# VEHICLE_RAW_SCH.net
KiCad netlist of a schematic drawn in Altium Designer
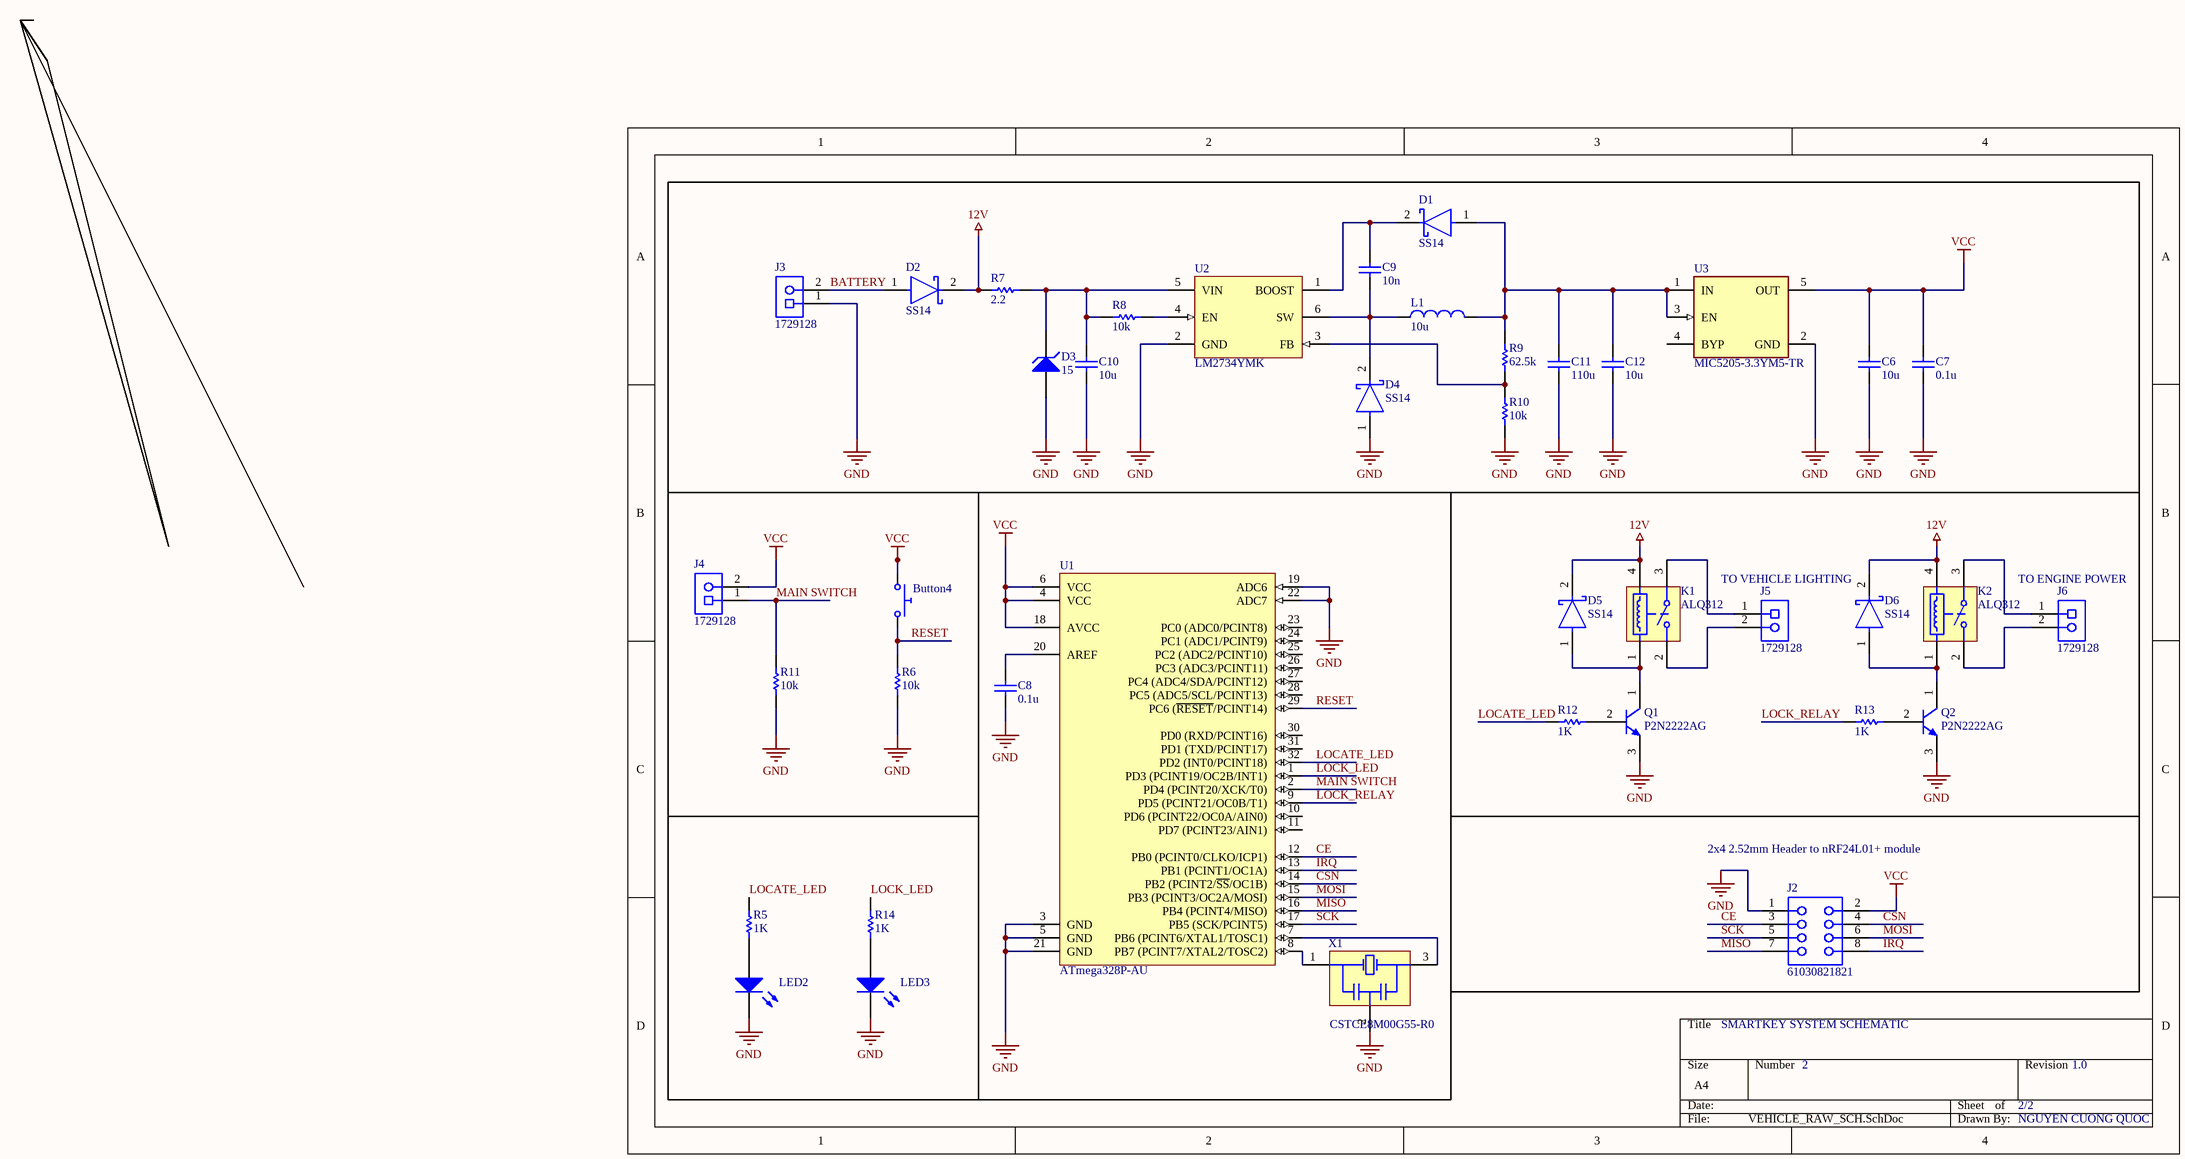
[diagram p0: VEHICLE_RAW_SCH.SchDoc]

(export (version "E")
  (design (tool "Eeschema 10.0.6"))
  (components
    (comp (ref "Button4")
      (value "Push Button Normally Opened")
      (libsource (lib "Simulation Generic Components") (part "Push Button NO"))
    )
    (comp (ref "C6")
      (value "10u")
      (description "Capacitor")
      (libsource (lib "Simulation Generic Components") (part "Capacitor"))
    )
    (comp (ref "C7")
      (value "0.1u")
      (description "Capacitor")
      (libsource (lib "Simulation Generic Components") (part "Capacitor"))
    )
    (comp (ref "C8")
      (value "0.1u")
      (description "Capacitor")
      (libsource (lib "Simulation Generic Components") (part "Capacitor"))
    )
    (comp (ref "C9")
      (value "10n")
      (description "Capacitor")
      (libsource (lib "Simulation Generic Components") (part "Capacitor"))
    )
    (comp (ref "C10")
      (value "10u")
      (description "Capacitor")
      (libsource (lib "Simulation Generic Components") (part "Capacitor"))
    )
    (comp (ref "C11")
      (value "110u")
      (description "Capacitor")
      (libsource (lib "Simulation Generic Components") (part "Capacitor"))
    )
    (comp (ref "C12")
      (value "10u")
      (description "Capacitor")
      (libsource (lib "Simulation Generic Components") (part "Capacitor"))
    )
    (comp (ref "D1")
      (value "SS14")
      (footprint "FP-403AE-MFG")
      (description "DIODE SCHOTTKY 40V 1A SMA")
      (fields
        (field (name "MANUFACTURER") "ON Semiconductor")
        (field (name "OCTOPART") "https://octopart.com/ss14-on+semiconductor-29205033")
      )
      (libsource (lib "Altium Content Vault") (part "360ad2f4ac25a952324d13796385471"))
    )
    (comp (ref "D2")
      (value "SS14")
      (footprint "FP-403AE-MFG")
      (description "DIODE SCHOTTKY 40V 1A SMA")
      (fields
        (field (name "MANUFACTURER") "ON Semiconductor")
        (field (name "OCTOPART") "https://octopart.com/ss14-on+semiconductor-29205033")
      )
      (libsource (lib "Altium Content Vault") (part "360ad2f4ac25a952324d13796385471"))
    )
    (comp (ref "D3")
      (value "Zener Diode")
      (fields (field (name "BV") "15"))
      (libsource (lib "Simulation Generic Components") (part "Zener Diode"))
    )
    (comp (ref "D4")
      (value "SS14")
      (footprint "FP-403AE-MFG")
      (description "DIODE SCHOTTKY 40V 1A SMA")
      (fields
        (field (name "MANUFACTURER") "ON Semiconductor")
        (field (name "OCTOPART") "https://octopart.com/ss14-on+semiconductor-29205033")
      )
      (libsource (lib "Altium Content Vault") (part "360ad2f4ac25a952324d13796385471"))
    )
    (comp (ref "D5")
      (value "SS14")
      (footprint "FP-403AE-MFG")
      (description "DIODE SCHOTTKY 40V 1A SMA")
      (fields
        (field (name "MANUFACTURER") "ON Semiconductor")
        (field (name "OCTOPART") "https://octopart.com/ss14-on+semiconductor-29205033")
      )
      (libsource (lib "Altium Content Vault") (part "360ad2f4ac25a952324d13796385471"))
    )
    (comp (ref "D6")
      (value "SS14")
      (footprint "FP-403AE-MFG")
      (description "DIODE SCHOTTKY 40V 1A SMA")
      (fields
        (field (name "MANUFACTURER") "ON Semiconductor")
        (field (name "OCTOPART") "https://octopart.com/ss14-on+semiconductor-29205033")
      )
      (libsource (lib "Altium Content Vault") (part "360ad2f4ac25a952324d13796385471"))
    )
    (comp (ref "J2")
      (value "61030821821")
      (footprint "61030821821")
      (libsource (lib "Altium Content Vault") (part "Header_Female_2R_08P"))
    )
    (comp (ref "J3")
      (value "1729128")
      (footprint "PHOE-1729128-2_V")
      (description "PCB Terminal Block, 13.5 A, 400 V, 2-Pin THD, RoHS, Bulk")
      (fields (field (name "MANUFACTURER") "Phoenix Contact"))
      (libsource (lib "") (part "CN-2P-F-R2_1"))
    )
    (comp (ref "J4")
      (value "1729128")
      (footprint "PHOE-1729128-2_V")
      (description "PCB Terminal Block, 13.5 A, 400 V, 2-Pin THD, RoHS, Bulk")
      (fields (field (name "MANUFACTURER") "Phoenix Contact"))
      (libsource (lib "") (part "CN-2P-F-R2_1"))
    )
    (comp (ref "J5")
      (value "1729128")
      (footprint "PHOE-1729128-2_V")
      (description "PCB Terminal Block, 13.5 A, 400 V, 2-Pin THD, RoHS, Bulk")
      (fields (field (name "MANUFACTURER") "Phoenix Contact"))
      (libsource (lib "Altium Content Vault") (part "CN-2P-F-R2"))
    )
    (comp (ref "J6")
      (value "1729128")
      (footprint "PHOE-1729128-2_V")
      (description "PCB Terminal Block, 13.5 A, 400 V, 2-Pin THD, RoHS, Bulk")
      (fields (field (name "MANUFACTURER") "Phoenix Contact"))
      (libsource (lib "Altium Content Vault") (part "CN-2P-F-R2"))
    )
    (comp (ref "K1")
      (value "ALQ312")
      (footprint "PNSC-LQ-4-2000x1000x1600_V")
      (fields (field (name "MANUFACTURER") "Panasonic"))
      (libsource (lib "Altium Content Vault") (part "PNSC-ALQ312-LQ-4-2000x1000x1600-4"))
    )
    (comp (ref "K2")
      (value "ALQ312")
      (footprint "PNSC-LQ-4-2000x1000x1600_V")
      (fields (field (name "MANUFACTURER") "Panasonic"))
      (libsource (lib "Altium Content Vault") (part "PNSC-ALQ312-LQ-4-2000x1000x1600-4"))
    )
    (comp (ref "L1")
      (value "10u")
      (description "Inductor")
      (libsource (lib "Simulation Generic Components") (part "Inductor"))
    )
    (comp (ref "LED2")
      (value "Light-Emitting Diode")
      (libsource (lib "Simulation Generic Components") (part "LED"))
    )
    (comp (ref "LED3")
      (value "Light-Emitting Diode")
      (libsource (lib "Simulation Generic Components") (part "LED"))
    )
    (comp (ref "Q1")
      (value "P2N2222AG")
      (footprint "ONSC-TO-92-3-29-11")
      (description "Amplifier Transistor, NPN Silicon, 3-Pin TO-92, Pb-Free, Bulk Box")
      (fields (field (name "MANUFACTURER") "On Semiconductor"))
      (libsource (lib "Altium Content Vault") (part "ONSC-NPN-C1B2E3-3"))
    )
    (comp (ref "Q2")
      (value "P2N2222AG")
      (footprint "ONSC-TO-92-3-29-11")
      (description "Amplifier Transistor, NPN Silicon, 3-Pin TO-92, Pb-Free, Bulk Box")
      (fields (field (name "MANUFACTURER") "On Semiconductor"))
      (libsource (lib "Altium Content Vault") (part "ONSC-NPN-C1B2E3-3"))
    )
    (comp (ref "R5")
      (value "1K")
      (description "Resistor")
      (libsource (lib "Simulation Generic Components") (part "Resistor"))
    )
    (comp (ref "R6")
      (value "10k")
      (description "Resistor")
      (libsource (lib "Simulation Generic Components") (part "Resistor"))
    )
    (comp (ref "R7")
      (value "2.2")
      (description "Resistor")
      (libsource (lib "Simulation Generic Components") (part "Resistor"))
    )
    (comp (ref "R8")
      (value "10k")
      (description "Resistor")
      (libsource (lib "Simulation Generic Components") (part "Resistor"))
    )
    (comp (ref "R9")
      (value "62.5k")
      (description "Resistor")
      (libsource (lib "Simulation Generic Components") (part "Resistor"))
    )
    (comp (ref "R10")
      (value "10k")
      (description "Resistor")
      (libsource (lib "Simulation Generic Components") (part "Resistor"))
    )
    (comp (ref "R11")
      (value "10k")
      (description "Resistor")
      (libsource (lib "Simulation Generic Components") (part "Resistor"))
    )
    (comp (ref "R12")
      (value "1K")
      (description "Resistor")
      (libsource (lib "Simulation Generic Components") (part "Resistor"))
    )
    (comp (ref "R13")
      (value "1K")
      (description "Resistor")
      (libsource (lib "Simulation Generic Components") (part "Resistor"))
    )
    (comp (ref "R14")
      (value "1K")
      (description "Resistor")
      (libsource (lib "Simulation Generic Components") (part "Resistor"))
    )
    (comp (ref "U1")
      (value "ATmega328P-AU")
      (footprint "32A_M")
      (libsource (lib "Altium Content Vault") (part "MC-8B-ATM48-SQ32"))
    )
    (comp (ref "U2")
      (value "LM2734YMK")
      (footprint "DDC0006A_M")
      (description "1A Load Step-Down DC-DC Regulator, 6-pin Tiny SOT23")
      (fields (field (name "MANUFACTURER") "Texas Instruments"))
      (libsource (lib "Altium Content Vault") (part "PM-DCDC-LM2734MK"))
    )
    (comp (ref "U3")
      (value "MIC5205-3.3YM5-TR")
      (footprint "FP-M5-MFG")
      (description "IC REG LINEAR 3.3V 150MA SOT23-5")
      (fields
        (field (name "MANUFACTURER") "Microchip")
        (field (name "OCTOPART") "https://octopart.com/mic5205-3.3ym5-tr-microchip-66802130")
      )
      (libsource (lib "Altium Content Vault") (part "b2bb7f462d557aec50a251fc6568b2e"))
    )
    (comp (ref "X1")
      (value "CSTCE8M00G55-R0")
      (footprint "MURA-CSTCE_G_A-3_V")
      (description "Ceramic Resonator, 8 MHz, +/- 0.5%, -20 to 80 degC, 3-Pin SMD, RoHS, Tape and Reel")
      (fields (field (name "TOLERANCE") "0.5%") (field (name "MANUFACTURER") "Murata"))
      (libsource (lib "Altium Content Vault") (part "MURA-CSTCE_G_A-3"))
    )
  )
  (nets
    (net (code "1") (name "/BATTERY") (class "Default")
      (node (ref "D2") (pin "1") (pinfunction "A_1") (pintype "passive"))
      (node (ref "J3") (pin "2") (pinfunction "2_2") (pintype "passive"))
    )
    (net (code "2") (name "/CE") (class "Default")
      (node (ref "J2") (pin "3") (pinfunction "3_3") (pintype "passive"))
      (node (ref "U1") (pin "12") (pinfunction "PB0_(PCINT0/CLKO/ICP1)_12") (pintype "bidirectional"))
    )
    (net (code "3") (name "/CSN") (class "Default")
      (node (ref "J2") (pin "4") (pinfunction "4_4") (pintype "passive"))
      (node (ref "U1") (pin "14") (pinfunction "PB2_(PCINT2/~{SS}/OC1B)_14") (pintype "bidirectional"))
    )
    (net (code "4") (name "/IRQ") (class "Default")
      (node (ref "J2") (pin "8") (pinfunction "8_8") (pintype "passive"))
      (node (ref "U1") (pin "13") (pinfunction "PB1_(PCINT1/OC1A)_13") (pintype "bidirectional"))
    )
    (net (code "5") (name "/LOCATE_LED") (class "Default")
      (node (ref "R12") (pin "2") (pinfunction "2_2") (pintype "passive"))
      (node (ref "R5") (pin "2") (pinfunction "2_2") (pintype "passive"))
      (node (ref "U1") (pin "32") (pinfunction "PD2_(INT0/PCINT18)_32") (pintype "bidirectional"))
    )
    (net (code "6") (name "/LOCK_LED") (class "Default")
      (node (ref "R14") (pin "2") (pinfunction "2_2") (pintype "passive"))
      (node (ref "U1") (pin "1") (pinfunction "PD3_(PCINT19/OC2B/INT1)_1") (pintype "bidirectional"))
    )
    (net (code "7") (name "/LOCK_RELAY") (class "Default")
      (node (ref "R13") (pin "2") (pinfunction "2_2") (pintype "passive"))
      (node (ref "U1") (pin "9") (pinfunction "PD5_(PCINT21/OC0B/T1)_9") (pintype "bidirectional"))
    )
    (net (code "8") (name "/MAIN SWITCH") (class "Default")
      (node (ref "J4") (pin "1") (pinfunction "1_1") (pintype "passive"))
      (node (ref "R11") (pin "2") (pinfunction "2_2") (pintype "passive"))
      (node (ref "U1") (pin "2") (pinfunction "PD4_(PCINT20/XCK/T0)_2") (pintype "bidirectional"))
    )
    (net (code "9") (name "/MISO") (class "Default")
      (node (ref "J2") (pin "7") (pinfunction "7_7") (pintype "passive"))
      (node (ref "U1") (pin "16") (pinfunction "PB4_(PCINT4/MISO)_16") (pintype "bidirectional"))
    )
    (net (code "10") (name "/MOSI") (class "Default")
      (node (ref "J2") (pin "6") (pinfunction "6_6") (pintype "passive"))
      (node (ref "U1") (pin "15") (pinfunction "PB3_(PCINT3/OC2A/MOSI)_15") (pintype "bidirectional"))
    )
    (net (code "11") (name "/RESET") (class "Default")
      (node (ref "Button4") (pin "2") (pinfunction "2_2") (pintype "passive"))
      (node (ref "R6") (pin "2") (pinfunction "2_2") (pintype "passive"))
      (node (ref "U1") (pin "29") (pinfunction "PC6_(~{RESET}/PCINT14)_29") (pintype "bidirectional"))
    )
    (net (code "12") (name "/SCK") (class "Default")
      (node (ref "J2") (pin "5") (pinfunction "5_5") (pintype "passive"))
      (node (ref "U1") (pin "17") (pinfunction "PB5_(SCK/PCINT5)_17") (pintype "bidirectional"))
    )
    (net (code "13") (name "12V") (class "Default")
      (node (ref "D2") (pin "2") (pinfunction "C_2") (pintype "passive"))
      (node (ref "D5") (pin "2") (pinfunction "C_2") (pintype "passive"))
      (node (ref "D6") (pin "2") (pinfunction "C_2") (pintype "passive"))
      (node (ref "K1") (pin "4") (pinfunction "4_4") (pintype "passive"))
      (node (ref "K2") (pin "4") (pinfunction "4_4") (pintype "passive"))
      (node (ref "R7") (pin "2") (pinfunction "2_2") (pintype "passive"))
    )
    (net (code "14") (name "GND") (class "Default")
      (node (ref "C10") (pin "1") (pinfunction "1_1") (pintype "passive"))
      (node (ref "C11") (pin "1") (pinfunction "1_1") (pintype "passive"))
      (node (ref "C12") (pin "1") (pinfunction "1_1") (pintype "passive"))
      (node (ref "C6") (pin "1") (pinfunction "1_1") (pintype "passive"))
      (node (ref "C7") (pin "1") (pinfunction "1_1") (pintype "passive"))
      (node (ref "C8") (pin "1") (pinfunction "1_1") (pintype "passive"))
      (node (ref "D3") (pin "1") (pinfunction "A_1") (pintype "passive"))
      (node (ref "D4") (pin "1") (pinfunction "A_1") (pintype "passive"))
      (node (ref "J2") (pin "1") (pinfunction "1_1") (pintype "passive"))
      (node (ref "J3") (pin "1") (pinfunction "1_1") (pintype "passive"))
      (node (ref "LED2") (pin "2") (pinfunction "K_2") (pintype "passive"))
      (node (ref "LED3") (pin "2") (pinfunction "K_2") (pintype "passive"))
      (node (ref "Q1") (pin "3") (pinfunction "E_3") (pintype "passive"))
      (node (ref "Q2") (pin "3") (pinfunction "E_3") (pintype "passive"))
      (node (ref "R10") (pin "2") (pinfunction "2_2") (pintype "passive"))
      (node (ref "R11") (pin "1") (pinfunction "1_1") (pintype "passive"))
      (node (ref "R6") (pin "1") (pinfunction "1_1") (pintype "passive"))
      (node (ref "U1") (pin "19") (pinfunction "ADC6_19") (pintype "input"))
      (node (ref "U1") (pin "21") (pinfunction "GND_21") (pintype "power_in"))
      (node (ref "U1") (pin "22") (pinfunction "ADC7_22") (pintype "input"))
      (node (ref "U1") (pin "3") (pinfunction "GND_3") (pintype "power_in"))
      (node (ref "U1") (pin "5") (pinfunction "GND_5") (pintype "power_in"))
      (node (ref "U2") (pin "2") (pinfunction "GND_2") (pintype "power_in"))
      (node (ref "U3") (pin "2") (pinfunction "GND_2") (pintype "power_in"))
      (node (ref "X1") (pin "2") (pinfunction "GND_2") (pintype "power_in"))
    )
    (net (code "15") (name "Net-(D1-A)") (class "Default")
      (node (ref "C11") (pin "2") (pinfunction "2_2") (pintype "passive"))
      (node (ref "C12") (pin "2") (pinfunction "2_2") (pintype "passive"))
      (node (ref "D1") (pin "1") (pinfunction "A_1") (pintype "passive"))
      (node (ref "L1") (pin "2") (pinfunction "2_2") (pintype "passive"))
      (node (ref "R9") (pin "1") (pinfunction "1_1") (pintype "passive"))
      (node (ref "U3") (pin "1") (pinfunction "IN_1") (pintype "power_in"))
      (node (ref "U3") (pin "3") (pinfunction "EN_3") (pintype "input"))
    )
    (net (code "16") (name "Net-(D1-C)") (class "Default")
      (node (ref "C9") (pin "2") (pinfunction "2_2") (pintype "passive"))
      (node (ref "D1") (pin "2") (pinfunction "C_2") (pintype "passive"))
      (node (ref "U2") (pin "1") (pinfunction "BOOST_1") (pintype "passive"))
    )
    (net (code "17") (name "Net-(D3-K)") (class "Default")
      (node (ref "C10") (pin "2") (pinfunction "2_2") (pintype "passive"))
      (node (ref "D3") (pin "2") (pinfunction "K_2") (pintype "passive"))
      (node (ref "R7") (pin "1") (pinfunction "1_1") (pintype "passive"))
      (node (ref "R8") (pin "2") (pinfunction "2_2") (pintype "passive"))
      (node (ref "U2") (pin "5") (pinfunction "VIN_5") (pintype "power_in"))
    )
    (net (code "18") (name "Net-(D4-C)") (class "Default")
      (node (ref "C9") (pin "1") (pinfunction "1_1") (pintype "passive"))
      (node (ref "D4") (pin "2") (pinfunction "C_2") (pintype "passive"))
      (node (ref "L1") (pin "1") (pinfunction "1_1") (pintype "passive"))
      (node (ref "U2") (pin "6") (pinfunction "SW_6") (pintype "power_in"))
    )
    (net (code "19") (name "Net-(D5-A)") (class "Default")
      (node (ref "D5") (pin "1") (pinfunction "A_1") (pintype "passive"))
      (node (ref "K1") (pin "1") (pinfunction "1_1") (pintype "passive"))
      (node (ref "Q1") (pin "1") (pinfunction "C_1") (pintype "passive"))
    )
    (net (code "20") (name "Net-(D6-A)") (class "Default")
      (node (ref "D6") (pin "1") (pinfunction "A_1") (pintype "passive"))
      (node (ref "K2") (pin "1") (pinfunction "1_1") (pintype "passive"))
      (node (ref "Q2") (pin "1") (pinfunction "C_1") (pintype "passive"))
    )
    (net (code "21") (name "Net-(K1-COM)") (class "Default")
      (node (ref "J5") (pin "1") (pinfunction "1_1") (pintype "passive"))
      (node (ref "K1") (pin "3") (pinfunction "COM_3") (pintype "passive"))
    )
    (net (code "22") (name "Net-(K1-NO)") (class "Default")
      (node (ref "J5") (pin "2") (pinfunction "2_2") (pintype "passive"))
      (node (ref "K1") (pin "2") (pinfunction "NO_2") (pintype "passive"))
    )
    (net (code "23") (name "Net-(K2-COM)") (class "Default")
      (node (ref "J6") (pin "1") (pinfunction "1_1") (pintype "passive"))
      (node (ref "K2") (pin "3") (pinfunction "COM_3") (pintype "passive"))
    )
    (net (code "24") (name "Net-(K2-NO)") (class "Default")
      (node (ref "J6") (pin "2") (pinfunction "2_2") (pintype "passive"))
      (node (ref "K2") (pin "2") (pinfunction "NO_2") (pintype "passive"))
    )
    (net (code "25") (name "Net-(LED2-A)") (class "Default")
      (node (ref "LED2") (pin "1") (pinfunction "A_1") (pintype "passive"))
      (node (ref "R5") (pin "1") (pinfunction "1_1") (pintype "passive"))
    )
    (net (code "26") (name "Net-(LED3-A)") (class "Default")
      (node (ref "LED3") (pin "1") (pinfunction "A_1") (pintype "passive"))
      (node (ref "R14") (pin "1") (pinfunction "1_1") (pintype "passive"))
    )
    (net (code "27") (name "Net-(Q1-B)") (class "Default")
      (node (ref "Q1") (pin "2") (pinfunction "B_2") (pintype "passive"))
      (node (ref "R12") (pin "1") (pinfunction "1_1") (pintype "passive"))
    )
    (net (code "28") (name "Net-(Q2-B)") (class "Default")
      (node (ref "Q2") (pin "2") (pinfunction "B_2") (pintype "passive"))
      (node (ref "R13") (pin "1") (pinfunction "1_1") (pintype "passive"))
    )
    (net (code "29") (name "Net-(U1-AREF)") (class "Default")
      (node (ref "C8") (pin "2") (pinfunction "2_2") (pintype "passive"))
      (node (ref "U1") (pin "20") (pinfunction "AREF_20") (pintype "passive"))
    )
    (net (code "30") (name "Net-(U1-PB6_(PCINT6{slash}XTAL1{slash}TOSC1))") (class "Default")
      (node (ref "U1") (pin "7") (pinfunction "PB6_(PCINT6/XTAL1/TOSC1)_7") (pintype "bidirectional"))
      (node (ref "X1") (pin "3") (pinfunction "X2_3") (pintype "passive"))
    )
    (net (code "31") (name "Net-(U1-PB7_(PCINT7{slash}XTAL2{slash}TOSC2))") (class "Default")
      (node (ref "U1") (pin "8") (pinfunction "PB7_(PCINT7/XTAL2/TOSC2)_8") (pintype "bidirectional"))
      (node (ref "X1") (pin "1") (pinfunction "X1_1") (pintype "passive"))
    )
    (net (code "32") (name "Net-(U2-EN)") (class "Default")
      (node (ref "R8") (pin "1") (pinfunction "1_1") (pintype "passive"))
      (node (ref "U2") (pin "4") (pinfunction "EN_4") (pintype "input"))
    )
    (net (code "33") (name "Net-(U2-FB)") (class "Default")
      (node (ref "R10") (pin "1") (pinfunction "1_1") (pintype "passive"))
      (node (ref "R9") (pin "2") (pinfunction "2_2") (pintype "passive"))
      (node (ref "U2") (pin "3") (pinfunction "FB_3") (pintype "input"))
    )
    (net (code "34") (name "VCC") (class "Default")
      (node (ref "Button4") (pin "1") (pinfunction "1_1") (pintype "passive"))
      (node (ref "C6") (pin "2") (pinfunction "2_2") (pintype "passive"))
      (node (ref "C7") (pin "2") (pinfunction "2_2") (pintype "passive"))
      (node (ref "J2") (pin "2") (pinfunction "2_2") (pintype "passive"))
      (node (ref "J4") (pin "2") (pinfunction "2_2") (pintype "passive"))
      (node (ref "U1") (pin "18") (pinfunction "AVCC_18") (pintype "power_in"))
      (node (ref "U1") (pin "4") (pinfunction "VCC_4") (pintype "power_in"))
      (node (ref "U1") (pin "6") (pinfunction "VCC_6") (pintype "power_in"))
      (node (ref "U3") (pin "5") (pinfunction "OUT_5") (pintype "power_in"))
    )
    (net (code "35") (name "unconnected-(U1-PC0_(ADC0{slash}PCINT8)-Pad23)") (class "Default")
      (node (ref "U1") (pin "23") (pinfunction "PC0_(ADC0/PCINT8)_23") (pintype "bidirectional"))
    )
    (net (code "36") (name "unconnected-(U1-PC1_(ADC1{slash}PCINT9)-Pad24)") (class "Default")
      (node (ref "U1") (pin "24") (pinfunction "PC1_(ADC1/PCINT9)_24") (pintype "bidirectional"))
    )
    (net (code "37") (name "unconnected-(U1-PC2_(ADC2{slash}PCINT10)-Pad25)") (class "Default")
      (node (ref "U1") (pin "25") (pinfunction "PC2_(ADC2/PCINT10)_25") (pintype "bidirectional"))
    )
    (net (code "38") (name "unconnected-(U1-PC3_(ADC3{slash}PCINT11)-Pad26)") (class "Default")
      (node (ref "U1") (pin "26") (pinfunction "PC3_(ADC3/PCINT11)_26") (pintype "bidirectional"))
    )
    (net (code "39") (name "unconnected-(U1-PC4_(ADC4{slash}SDA{slash}PCINT12)-Pad27)") (class "Default")
      (node (ref "U1") (pin "27") (pinfunction "PC4_(ADC4/SDA/PCINT12)_27") (pintype "bidirectional"))
    )
    (net (code "40") (name "unconnected-(U1-PC5_(ADC5{slash}SCL{slash}PCINT13)-Pad28)") (class "Default")
      (node (ref "U1") (pin "28") (pinfunction "PC5_(ADC5/SCL/PCINT13)_28") (pintype "bidirectional"))
    )
    (net (code "41") (name "unconnected-(U1-PD0_(RXD{slash}PCINT16)-Pad30)") (class "Default")
      (node (ref "U1") (pin "30") (pinfunction "PD0_(RXD/PCINT16)_30") (pintype "bidirectional"))
    )
    (net (code "42") (name "unconnected-(U1-PD1_(TXD{slash}PCINT17)-Pad31)") (class "Default")
      (node (ref "U1") (pin "31") (pinfunction "PD1_(TXD/PCINT17)_31") (pintype "bidirectional"))
    )
    (net (code "43") (name "unconnected-(U1-PD6_(PCINT22{slash}OC0A{slash}AIN0)-Pad10)") (class "Default")
      (node (ref "U1") (pin "10") (pinfunction "PD6_(PCINT22/OC0A/AIN0)_10") (pintype "bidirectional"))
    )
    (net (code "44") (name "unconnected-(U1-PD7_(PCINT23{slash}AIN1)-Pad11)") (class "Default")
      (node (ref "U1") (pin "11") (pinfunction "PD7_(PCINT23/AIN1)_11") (pintype "bidirectional"))
    )
    (net (code "45") (name "unconnected-(U3-BYP-Pad4)") (class "Default")
      (node (ref "U3") (pin "4") (pinfunction "BYP_4") (pintype "passive"))
    )
  )
)
